# MICRO.net
KiCad netlist of a schematic drawn in Altium Designer
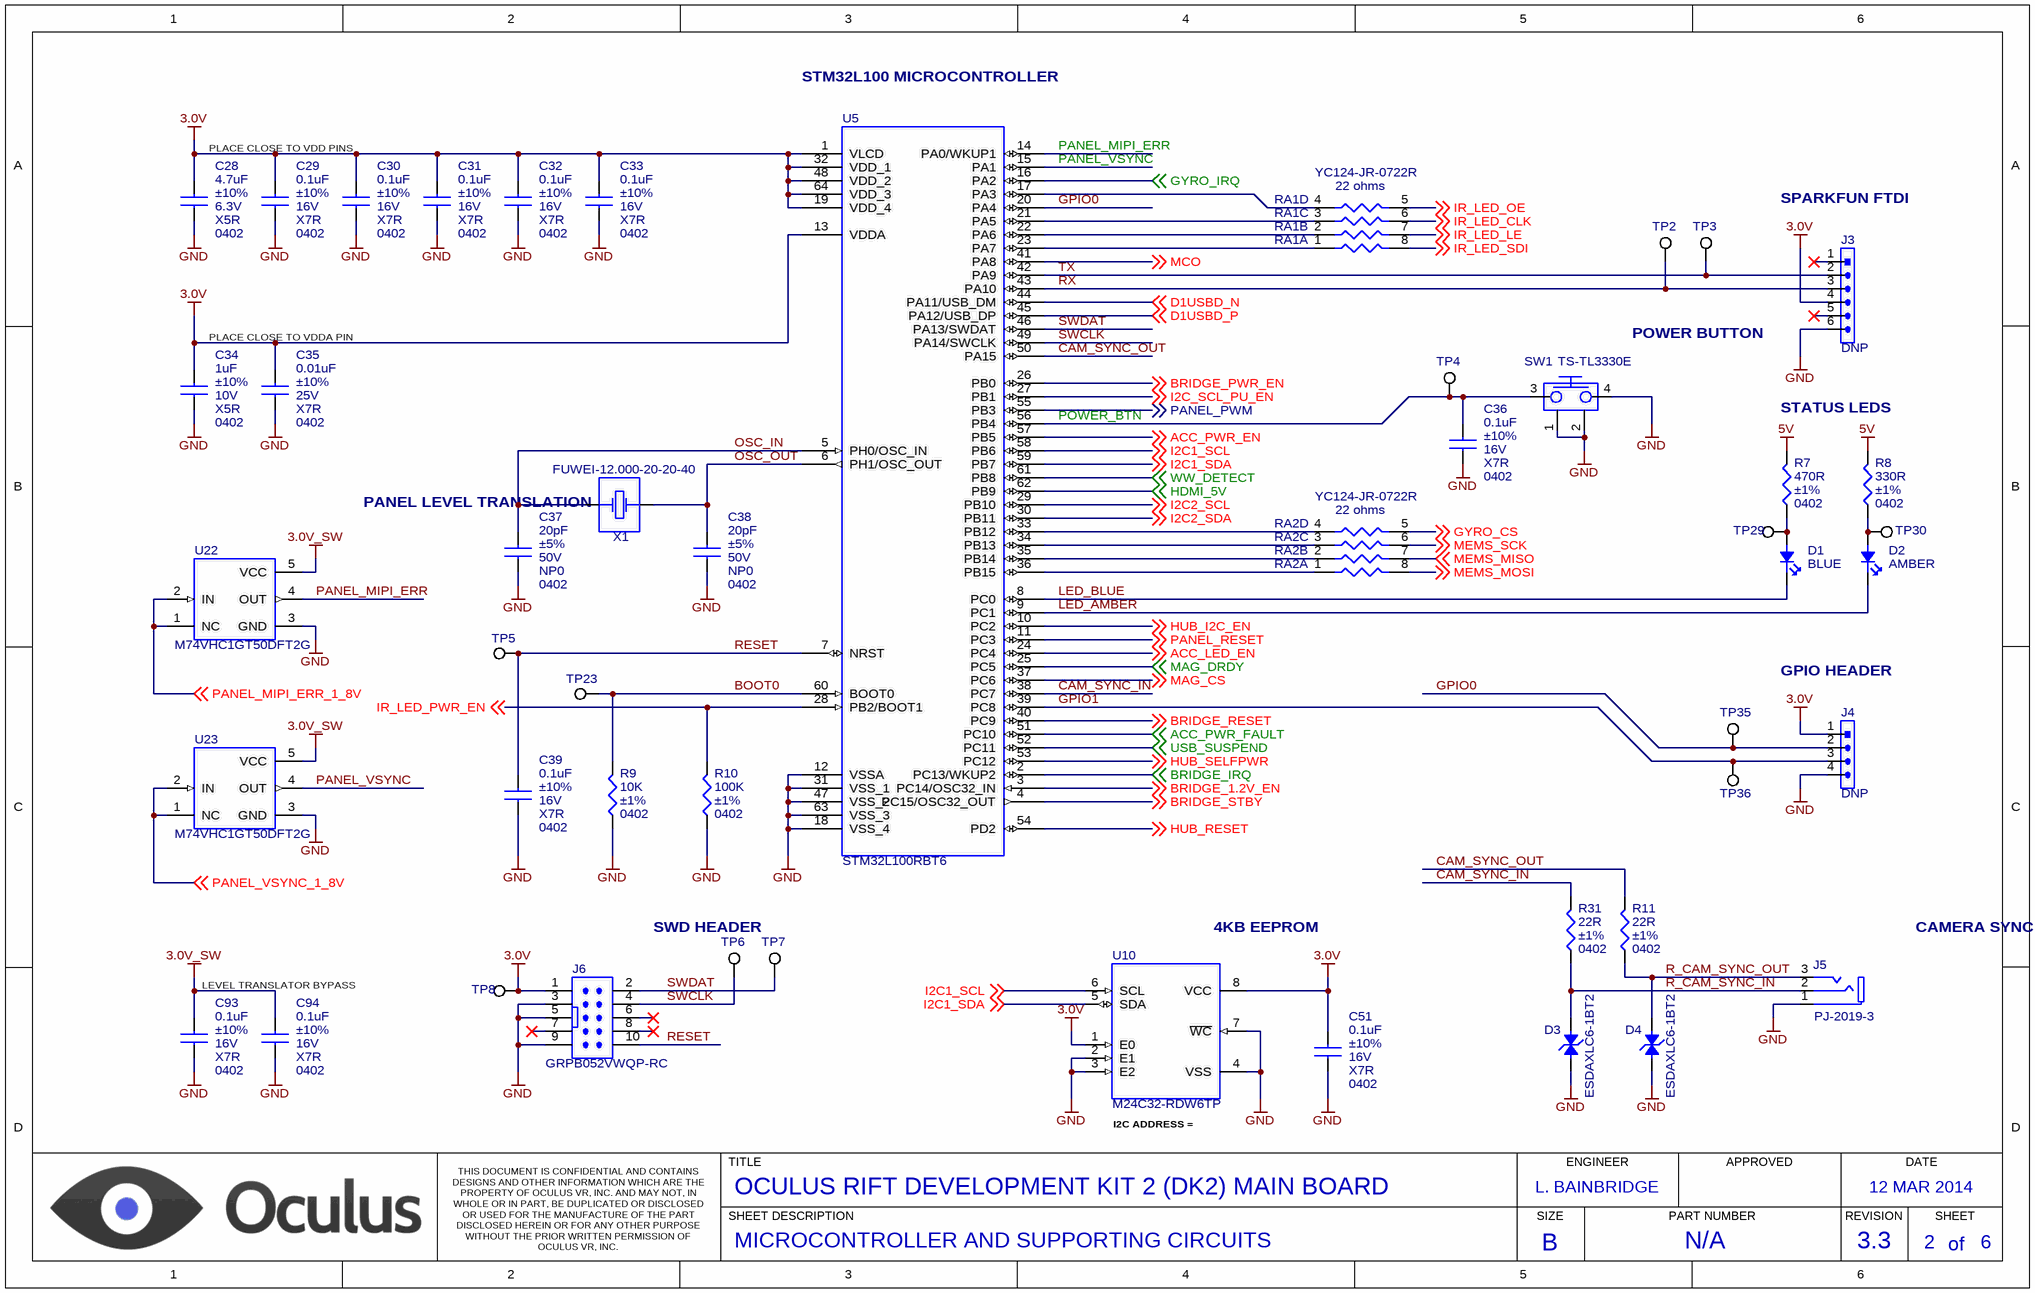
[diagram p0: MICRO.SchDoc]

(export (version "E")
  (design (tool "Eeschema 10.0.6"))
  (components
    (comp (ref "C28")
      (value "4.7uF")
      (footprint "CAP_CERAMIC_0402")
      (description "CAP, CERAMIC, 4.7uF, ±10%, 6.3V, X5R, 0402")
      (fields
        (field (name "MANUFACTURER") "TDK CORPORATION")
        (field (name "PART NUMBER") "C1005X5R0J475K")
        (field (name "TOLERANCE") "±10%")
        (field (name "VOLTAGE") "6.3V")
        (field (name "DIELECTRIC") "X5R")
        (field (name "PACKAGE") "0402")
      )
      (libsource (lib "DK2") (part "CAP, CERAMIC"))
    )
    (comp (ref "C29")
      (value "0.1uF")
      (footprint "CAP_CERAMIC_0402")
      (description "CAP, CERAMIC, 0.1uF, ±10%, 16V, X7R, 0402")
      (fields
        (field (name "MANUFACTURER") "MURATA ELECTRONICS")
        (field (name "PART NUMBER") "GRM155R71C104KA88D")
        (field (name "TOLERANCE") "±10%")
        (field (name "VOLTAGE") "16V")
        (field (name "DIELECTRIC") "X7R")
        (field (name "PACKAGE") "0402")
      )
      (libsource (lib "DK2") (part "CAP, CERAMIC"))
    )
    (comp (ref "C30")
      (value "0.1uF")
      (footprint "CAP_CERAMIC_0402")
      (description "CAP, CERAMIC, 0.1uF, ±10%, 16V, X7R, 0402")
      (fields
        (field (name "MANUFACTURER") "MURATA ELECTRONICS")
        (field (name "PART NUMBER") "GRM155R71C104KA88D")
        (field (name "TOLERANCE") "±10%")
        (field (name "VOLTAGE") "16V")
        (field (name "DIELECTRIC") "X7R")
        (field (name "PACKAGE") "0402")
      )
      (libsource (lib "DK2") (part "CAP, CERAMIC"))
    )
    (comp (ref "C31")
      (value "0.1uF")
      (footprint "CAP_CERAMIC_0402")
      (description "CAP, CERAMIC, 0.1uF, ±10%, 16V, X7R, 0402")
      (fields
        (field (name "MANUFACTURER") "MURATA ELECTRONICS")
        (field (name "PART NUMBER") "GRM155R71C104KA88D")
        (field (name "TOLERANCE") "±10%")
        (field (name "VOLTAGE") "16V")
        (field (name "DIELECTRIC") "X7R")
        (field (name "PACKAGE") "0402")
      )
      (libsource (lib "DK2") (part "CAP, CERAMIC"))
    )
    (comp (ref "C32")
      (value "0.1uF")
      (footprint "CAP_CERAMIC_0402")
      (description "CAP, CERAMIC, 0.1uF, ±10%, 16V, X7R, 0402")
      (fields
        (field (name "MANUFACTURER") "MURATA ELECTRONICS")
        (field (name "PART NUMBER") "GRM155R71C104KA88D")
        (field (name "TOLERANCE") "±10%")
        (field (name "VOLTAGE") "16V")
        (field (name "DIELECTRIC") "X7R")
        (field (name "PACKAGE") "0402")
      )
      (libsource (lib "DK2") (part "CAP, CERAMIC"))
    )
    (comp (ref "C33")
      (value "0.1uF")
      (footprint "CAP_CERAMIC_0402")
      (description "CAP, CERAMIC, 0.1uF, ±10%, 16V, X7R, 0402")
      (fields
        (field (name "MANUFACTURER") "MURATA ELECTRONICS")
        (field (name "PART NUMBER") "GRM155R71C104KA88D")
        (field (name "TOLERANCE") "±10%")
        (field (name "VOLTAGE") "16V")
        (field (name "DIELECTRIC") "X7R")
        (field (name "PACKAGE") "0402")
      )
      (libsource (lib "DK2") (part "CAP, CERAMIC"))
    )
    (comp (ref "C34")
      (value "1uF")
      (footprint "CAP_CERAMIC_0402")
      (description "CAP, CERAMIC, 1uF, ±10%, 10V, X5R, 0402")
      (fields
        (field (name "MANUFACTURER") "MURATA ELECTRONICS")
        (field (name "PART NUMBER") "GRM155R61A105KE15D")
        (field (name "TOLERANCE") "±10%")
        (field (name "VOLTAGE") "10V")
        (field (name "DIELECTRIC") "X5R")
        (field (name "PACKAGE") "0402")
      )
      (libsource (lib "DK2") (part "CAP, CERAMIC"))
    )
    (comp (ref "C35")
      (value "0.01uF")
      (footprint "CAP_CERAMIC_0402")
      (description "CAP, CERAMIC, 0.01uF, ±10%, 25V, X7R, 0402")
      (fields
        (field (name "MANUFACTURER") "MURATA ELECTRONICS")
        (field (name "PART NUMBER") "GRM155R71E103KA01D")
        (field (name "TOLERANCE") "±10%")
        (field (name "VOLTAGE") "25V")
        (field (name "DIELECTRIC") "X7R")
        (field (name "PACKAGE") "0402")
      )
      (libsource (lib "DK2") (part "CAP, CERAMIC"))
    )
    (comp (ref "C36")
      (value "0.1uF")
      (footprint "CAP_CERAMIC_0402")
      (description "CAP, CERAMIC, 0.1uF, ±10%, 16V, X7R, 0402")
      (fields
        (field (name "MANUFACTURER") "MURATA ELECTRONICS")
        (field (name "PART NUMBER") "GRM155R71C104KA88D")
        (field (name "TOLERANCE") "±10%")
        (field (name "VOLTAGE") "16V")
        (field (name "DIELECTRIC") "X7R")
        (field (name "PACKAGE") "0402")
      )
      (libsource (lib "DK2") (part "CAP, CERAMIC"))
    )
    (comp (ref "C37")
      (value "20pF")
      (footprint "CAP_CERAMIC_0402")
      (description "CAP, CERAMIC, 20pF, ±5%, 50V, NP0, 0402")
      (fields
        (field (name "MANUFACTURER") "MURATA ELECTRONICS")
        (field (name "PART NUMBER") "GRM1555C1H200JA01D")
        (field (name "TOLERANCE") "±5%")
        (field (name "VOLTAGE") "50V")
        (field (name "DIELECTRIC") "NP0")
        (field (name "PACKAGE") "0402")
      )
      (libsource (lib "DK2") (part "CAP, CERAMIC"))
    )
    (comp (ref "C38")
      (value "20pF")
      (footprint "CAP_CERAMIC_0402")
      (description "CAP, CERAMIC, 20pF, ±5%, 50V, NP0, 0402")
      (fields
        (field (name "MANUFACTURER") "MURATA ELECTRONICS")
        (field (name "PART NUMBER") "GRM1555C1H200JA01D")
        (field (name "TOLERANCE") "±5%")
        (field (name "VOLTAGE") "50V")
        (field (name "DIELECTRIC") "NP0")
        (field (name "PACKAGE") "0402")
      )
      (libsource (lib "DK2") (part "CAP, CERAMIC"))
    )
    (comp (ref "C39")
      (value "0.1uF")
      (footprint "CAP_CERAMIC_0402")
      (description "CAP, CERAMIC, 0.1uF, ±10%, 16V, X7R, 0402")
      (fields
        (field (name "MANUFACTURER") "MURATA ELECTRONICS")
        (field (name "PART NUMBER") "GRM155R71C104KA88D")
        (field (name "TOLERANCE") "±10%")
        (field (name "VOLTAGE") "16V")
        (field (name "DIELECTRIC") "X7R")
        (field (name "PACKAGE") "0402")
      )
      (libsource (lib "DK2") (part "CAP, CERAMIC"))
    )
    (comp (ref "C51")
      (value "0.1uF")
      (footprint "CAP_CERAMIC_0402")
      (description "CAP, CERAMIC, 0.1uF, ±10%, 16V, X7R, 0402")
      (fields
        (field (name "MANUFACTURER") "MURATA ELECTRONICS")
        (field (name "PART NUMBER") "GRM155R71C104KA88D")
        (field (name "TOLERANCE") "±10%")
        (field (name "VOLTAGE") "16V")
        (field (name "DIELECTRIC") "X7R")
        (field (name "PACKAGE") "0402")
      )
      (libsource (lib "DK2") (part "CAP, CERAMIC"))
    )
    (comp (ref "C93")
      (value "0.1uF")
      (footprint "CAP_CERAMIC_0402")
      (description "CAP, CERAMIC, 0.1uF, ±10%, 16V, X7R, 0402")
      (fields
        (field (name "MANUFACTURER") "MURATA ELECTRONICS")
        (field (name "PART NUMBER") "GRM155R71C104KA88D")
        (field (name "TOLERANCE") "±10%")
        (field (name "VOLTAGE") "16V")
        (field (name "DIELECTRIC") "X7R")
        (field (name "PACKAGE") "0402")
      )
      (libsource (lib "DK2") (part "CAP, CERAMIC"))
    )
    (comp (ref "C94")
      (value "0.1uF")
      (footprint "CAP_CERAMIC_0402")
      (description "CAP, CERAMIC, 0.1uF, ±10%, 16V, X7R, 0402")
      (fields
        (field (name "MANUFACTURER") "MURATA ELECTRONICS")
        (field (name "PART NUMBER") "GRM155R71C104KA88D")
        (field (name "TOLERANCE") "±10%")
        (field (name "VOLTAGE") "16V")
        (field (name "DIELECTRIC") "X7R")
        (field (name "PACKAGE") "0402")
      )
      (libsource (lib "DK2") (part "CAP, CERAMIC"))
    )
    (comp (ref "D1")
      (value "LED")
      (footprint "LED_BLUE_0603")
      (description "LED, BLUE, 0603")
      (fields
        (field (name "MANUFACTURER") "PANASONIC")
        (field (name "PART NUMBER") "LNJ926W8CRA")
        (field (name "COLOR") "BLUE")
      )
      (libsource (lib "DK2") (part "LED"))
    )
    (comp (ref "D2")
      (value "LED")
      (footprint "LED_AMBER_0603")
      (description "LED, AMBER, 0603")
      (fields
        (field (name "MANUFACTURER") "PANASONIC")
        (field (name "PART NUMBER") "LNJ437W84RA")
        (field (name "COLOR") "AMBER")
      )
      (libsource (lib "DK2") (part "LED"))
    )
    (comp (ref "D3")
      (value "ESDAXLC6-1BT2")
      (footprint "SOD-882T")
      (description "DIODE, ESD SUPPRESSOR, SINGLE LINE BI-DIRECTIONAL, LOW CAPACITANCE")
      (fields (field (name "MANUFACTURER") "ST MICROELECTRONICS"))
      (libsource (lib "DK2") (part "ESDAXLC6-1BT2"))
    )
    (comp (ref "D4")
      (value "ESDAXLC6-1BT2")
      (footprint "SOD-882T")
      (description "DIODE, ESD SUPPRESSOR, SINGLE LINE BI-DIRECTIONAL, LOW CAPACITANCE")
      (fields (field (name "MANUFACTURER") "ST MICROELECTRONICS"))
      (libsource (lib "DK2") (part "ESDAXLC6-1BT2"))
    )
    (comp (ref "J3")
      (value "DNP")
      (footprint "HEADER_1X6")
      (description "CONNECTOR, HEADER, 6 POS, 1X6, 0.1\" PITCH")
      (fields (field (name "MANUFACTURER") "TBD"))
      (libsource (lib "DK2") (part "HEADER 1X6"))
    )
    (comp (ref "J4")
      (value "DNP")
      (footprint "HEADER_1X4")
      (description "CONNECTOR, HEADER, 4 POS, 1X4, 0.1\" PITCH")
      (fields (field (name "MANUFACTURER") "TBD"))
      (libsource (lib "DK2") (part "HEADER 1X4"))
    )
    (comp (ref "J5")
      (value "PJ-2019-3")
      (footprint "PJ-2019-3")
      (description "CONNECTOR, 2.5MM STEREO AUDIO JACK")
      (fields (field (name "MANUFACTURER") "BERWAY TECHNOLOGY"))
      (libsource (lib "DK2") (part "PJ-2019-3"))
    )
    (comp (ref "J6")
      (value "GRPB052VWQP-RC")
      (footprint "GRPB052VWQP-RC")
      (description "CONNECTOR, 10 POS, ARM CORTEX SWD HEADER")
      (fields (field (name "MANUFACTURER") "SULLINS CONNECTOR"))
      (libsource (lib "DK2") (part "GRPB052VWQP-RC"))
    )
    (comp (ref "R7")
      (value "470R")
      (footprint "RESISTOR_0402")
      (description "RES, 470 OHM, 1/10W, ±1%, 0402")
      (fields
        (field (name "MANUFACTURER") "PANASONIC")
        (field (name "PART NUMBER") "ERJ-2RKF4700X")
        (field (name "PACKAGE") "0402")
        (field (name "TOLERANCE") "±1%")
      )
      (libsource (lib "DK2") (part "RESISTOR"))
    )
    (comp (ref "R8")
      (value "330R")
      (footprint "RESISTOR_0402")
      (description "RES, 330 OHM, 1/10W, ±1%, 0402")
      (fields
        (field (name "MANUFACTURER") "PANASONIC")
        (field (name "PART NUMBER") "ERJ-2RKF3300X")
        (field (name "PACKAGE") "0402")
        (field (name "TOLERANCE") "±1%")
      )
      (libsource (lib "DK2") (part "RESISTOR"))
    )
    (comp (ref "R9")
      (value "10K")
      (footprint "RESISTOR_0402")
      (description "RES, 10K OHM, 1/10W, ±1%, 0402")
      (fields
        (field (name "MANUFACTURER") "PANASONIC")
        (field (name "PART NUMBER") "ERJ-2RKF1002X")
        (field (name "PACKAGE") "0402")
        (field (name "TOLERANCE") "±1%")
      )
      (libsource (lib "DK2") (part "RESISTOR"))
    )
    (comp (ref "R10")
      (value "100K")
      (footprint "RESISTOR_0402")
      (description "RES, 100K OHM, 1/10W, ±1%, 0402")
      (fields
        (field (name "MANUFACTURER") "PANASONIC")
        (field (name "PART NUMBER") "ERJ-2RKF1003X")
        (field (name "PACKAGE") "0402")
        (field (name "TOLERANCE") "±1%")
      )
      (libsource (lib "DK2") (part "RESISTOR"))
    )
    (comp (ref "R11")
      (value "22R")
      (footprint "RESISTOR_0402")
      (description "RES, 22 OHM, 1/10W, ±1%, 0402")
      (fields
        (field (name "MANUFACTURER") "PANASONIC")
        (field (name "PART NUMBER") "ERJ-2RKF22R0X")
        (field (name "PACKAGE") "0402")
        (field (name "TOLERANCE") "±1%")
      )
      (libsource (lib "DK2") (part "RESISTOR"))
    )
    (comp (ref "R31")
      (value "22R")
      (footprint "RESISTOR_0402")
      (description "RES, 22 OHM, 1/10W, ±1%, 0402")
      (fields
        (field (name "MANUFACTURER") "PANASONIC")
        (field (name "PART NUMBER") "ERJ-2RKF22R0X")
        (field (name "PACKAGE") "0402")
        (field (name "TOLERANCE") "±1%")
      )
      (libsource (lib "DK2") (part "RESISTOR"))
    )
    (comp (ref "RA1")
      (value "YC124-JR-0722R")
      (footprint "YC124")
      (description "RESISTOR ARRAY, 4 RESISTORS, 22 OHM, 5%, 0.5MM PITCH")
      (fields (field (name "MANUFACTURER") "YAGEO") (field (name "ALTIUM_VALUE") "22 ohms"))
      (libsource (lib "DK2") (part "YC124-JR-0722R"))
    )
    (comp (ref "RA2")
      (value "YC124-JR-0722R")
      (footprint "YC124")
      (description "RESISTOR ARRAY, 4 RESISTORS, 22 OHM, 5%, 0.5MM PITCH")
      (fields (field (name "MANUFACTURER") "YAGEO") (field (name "ALTIUM_VALUE") "22 ohms"))
      (libsource (lib "DK2") (part "YC124-JR-0722R"))
    )
    (comp (ref "SW1")
      (value "TS-TL3330E")
      (footprint "TS-TL3330E")
      (description "SWITCH, TACTILE, SPST-NO, 250gf")
      (fields (field (name "MANUFACTURER") "BERWAY TECHNOLOGY"))
      (libsource (lib "DK2") (part "TS-TL3330E"))
    )
    (comp (ref "TP2")
      (value "TEST POINT")
      (footprint "TEST_POINT_PAD_1.2X3MM")
      (libsource (lib "DK2") (part "TEST_POINT_GENERIC"))
    )
    (comp (ref "TP3")
      (value "TEST POINT")
      (footprint "TEST_POINT_PAD_1.2X3MM")
      (libsource (lib "DK2") (part "TEST_POINT_GENERIC"))
    )
    (comp (ref "TP4")
      (value "TEST POINT")
      (footprint "TEST_POINT_PAD_1MM")
      (libsource (lib "DK2") (part "TEST_POINT_GENERIC"))
    )
    (comp (ref "TP5")
      (value "TEST POINT")
      (footprint "TEST_POINT_PAD_1MM")
      (libsource (lib "DK2") (part "TEST_POINT_GENERIC"))
    )
    (comp (ref "TP6")
      (value "TEST POINT")
      (footprint "TEST_POINT_PAD_1MM")
      (libsource (lib "DK2") (part "TEST_POINT_GENERIC"))
    )
    (comp (ref "TP7")
      (value "TEST POINT")
      (footprint "TEST_POINT_PAD_1MM")
      (libsource (lib "DK2") (part "TEST_POINT_GENERIC"))
    )
    (comp (ref "TP8")
      (value "TEST POINT")
      (footprint "TEST_POINT_PAD_1MM")
      (libsource (lib "DK2") (part "TEST_POINT_GENERIC"))
    )
    (comp (ref "TP23")
      (value "TEST POINT")
      (footprint "TEST_POINT_PAD_1MM")
      (libsource (lib "DK2") (part "TEST_POINT_GENERIC"))
    )
    (comp (ref "TP29")
      (value "TEST POINT")
      (footprint "TEST_POINT_PAD_1MM")
      (libsource (lib "DK2") (part "TEST_POINT_GENERIC"))
    )
    (comp (ref "TP30")
      (value "TEST POINT")
      (footprint "TEST_POINT_PAD_1MM")
      (libsource (lib "DK2") (part "TEST_POINT_GENERIC"))
    )
    (comp (ref "TP35")
      (value "TEST POINT")
      (footprint "TEST_POINT_PAD_1.2X3MM")
      (libsource (lib "DK2") (part "TEST_POINT_GENERIC"))
    )
    (comp (ref "TP36")
      (value "TEST POINT")
      (footprint "TEST_POINT_PAD_1MM")
      (libsource (lib "DK2") (part "TEST_POINT_GENERIC"))
    )
    (comp (ref "U5")
      (value "STM32L100RBT6")
      (footprint "LQFP64")
      (description "IC, STM32L MICROCONTROLLER, ARM CORTEX M3")
      (fields (field (name "MANUFACTURER") "ST MICROELECTRONICS"))
      (libsource (lib "DK2") (part "STM32L100RBT6"))
    )
    (comp (ref "U10")
      (value "M24C32-RDW6TP")
      (footprint "TSSOP8")
      (description "IC, EEPROM, I2C, 32 Kbits")
      (fields (field (name "MANUFACTURER") "STMICROELECTRONICS"))
      (libsource (lib "DK2") (part "M24C32-RDW6TP"))
    )
    (comp (ref "U22")
      (value "M74VHC1GT50DFT2G")
      (footprint "SC70-5")
      (description "IC, NON-INVERTING BUFFER, CMOS LOGIC LEVEL SHIFTER")
      (fields (field (name "MANUFACTURER") "ON SEMICONDUCTOR"))
      (libsource (lib "DK2") (part "M74VHC1GT50DFT2G"))
    )
    (comp (ref "U23")
      (value "M74VHC1GT50DFT2G")
      (footprint "SC70-5")
      (description "IC, NON-INVERTING BUFFER, CMOS LOGIC LEVEL SHIFTER")
      (fields (field (name "MANUFACTURER") "ON SEMICONDUCTOR"))
      (libsource (lib "DK2") (part "M74VHC1GT50DFT2G"))
    )
    (comp (ref "X1")
      (value "FUWEI-12.000-20-20-40")
      (footprint "HC-49USX")
      (description "CRYSTAL, 12MHZ, +/-30PPM, 20pF, HC-49USX")
      (fields (field (name "MANUFACTURER") "BERWAY TECHNOLOGY"))
      (libsource (lib "DK2") (part "FUWEI-12.000-20-20-40"))
    )
  )
  (nets
    (net (code "1") (name "/BOOT0") (class "Default")
      (node (ref "R9") (pin "2") (pinfunction "2_2") (pintype "passive"))
      (node (ref "TP23") (pin "1") (pinfunction "1_1") (pintype "passive"))
      (node (ref "U5") (pin "60") (pinfunction "BOOT0_60") (pintype "input"))
    )
    (net (code "2") (name "/CAM_SYNC_IN") (class "Default")
      (node (ref "R31") (pin "1") (pinfunction "1_1") (pintype "passive"))
      (node (ref "U5") (pin "38") (pinfunction "PC7_38") (pintype "bidirectional"))
    )
    (net (code "3") (name "/CAM_SYNC_OUT") (class "Default")
      (node (ref "R11") (pin "1") (pinfunction "1_1") (pintype "passive"))
      (node (ref "U5") (pin "50") (pinfunction "PA15_50") (pintype "bidirectional"))
    )
    (net (code "4") (name "/GPIO0") (class "Default")
      (node (ref "J4") (pin "2") (pintype "passive"))
      (node (ref "TP35") (pin "1") (pinfunction "1_1") (pintype "passive"))
      (node (ref "U5") (pin "20") (pinfunction "PA4_20") (pintype "bidirectional"))
    )
    (net (code "5") (name "/GPIO1") (class "Default")
      (node (ref "J4") (pin "3") (pintype "passive"))
      (node (ref "TP36") (pin "1") (pinfunction "1_1") (pintype "passive"))
      (node (ref "U5") (pin "39") (pinfunction "PC8_39") (pintype "bidirectional"))
    )
    (net (code "6") (name "/LED_AMBER") (class "Default")
      (node (ref "D2") (pin "2") (pinfunction "K_2") (pintype "passive"))
      (node (ref "U5") (pin "9") (pinfunction "PC1_9") (pintype "bidirectional"))
    )
    (net (code "7") (name "/LED_BLUE") (class "Default")
      (node (ref "D1") (pin "2") (pinfunction "K_2") (pintype "passive"))
      (node (ref "U5") (pin "8") (pinfunction "PC0_8") (pintype "bidirectional"))
    )
    (net (code "8") (name "/OSC_IN") (class "Default")
      (node (ref "C37") (pin "1") (pinfunction "1_1") (pintype "passive"))
      (node (ref "U5") (pin "5") (pinfunction "PH0/OSC_IN_5") (pintype "input"))
      (node (ref "X1") (pin "1") (pinfunction "1_1") (pintype "passive"))
    )
    (net (code "9") (name "/OSC_OUT") (class "Default")
      (node (ref "C38") (pin "1") (pinfunction "1_1") (pintype "passive"))
      (node (ref "U5") (pin "6") (pinfunction "PH1/OSC_OUT_6") (pintype "output"))
      (node (ref "X1") (pin "2") (pinfunction "3_2") (pintype "passive"))
    )
    (net (code "10") (name "/PANEL_MIPI_ERR") (class "Default")
      (node (ref "U22") (pin "4") (pinfunction "OUT_4") (pintype "output"))
      (node (ref "U5") (pin "14") (pinfunction "PA0/WKUP1_14") (pintype "bidirectional"))
    )
    (net (code "11") (name "/PANEL_VSYNC") (class "Default")
      (node (ref "U23") (pin "4") (pinfunction "OUT_4") (pintype "output"))
      (node (ref "U5") (pin "15") (pinfunction "PA1_15") (pintype "bidirectional"))
    )
    (net (code "12") (name "/POWER_BTN") (class "Default")
      (node (ref "C36") (pin "1") (pinfunction "1_1") (pintype "passive"))
      (node (ref "SW1") (pin "3") (pintype "passive"))
      (node (ref "TP4") (pin "1") (pinfunction "1_1") (pintype "passive"))
      (node (ref "U5") (pin "56") (pinfunction "PB4_56") (pintype "bidirectional"))
    )
    (net (code "13") (name "/RESET") (class "Default")
      (node (ref "C39") (pin "1") (pinfunction "1_1") (pintype "passive"))
      (node (ref "J6") (pin "10") (pintype "passive"))
      (node (ref "TP5") (pin "1") (pinfunction "1_1") (pintype "passive"))
      (node (ref "U5") (pin "7") (pinfunction "NRST_7") (pintype "bidirectional"))
    )
    (net (code "14") (name "/RX") (class "Default")
      (node (ref "J3") (pin "3") (pintype "passive"))
      (node (ref "TP2") (pin "1") (pinfunction "1_1") (pintype "passive"))
      (node (ref "U5") (pin "43") (pinfunction "PA10_43") (pintype "bidirectional"))
    )
    (net (code "15") (name "/R_CAM_SYNC_IN") (class "Default")
      (node (ref "D3") (pin "1") (pintype "passive"))
      (node (ref "J5") (pin "2") (pinfunction "2_2") (pintype "passive"))
      (node (ref "R31") (pin "2") (pinfunction "2_2") (pintype "passive"))
    )
    (net (code "16") (name "/R_CAM_SYNC_OUT") (class "Default")
      (node (ref "D4") (pin "1") (pintype "passive"))
      (node (ref "J5") (pin "3") (pinfunction "3_3") (pintype "passive"))
      (node (ref "R11") (pin "2") (pinfunction "2_2") (pintype "passive"))
    )
    (net (code "17") (name "/SWCLK") (class "Default")
      (node (ref "J6") (pin "4") (pintype "passive"))
      (node (ref "TP6") (pin "1") (pinfunction "1_1") (pintype "passive"))
      (node (ref "U5") (pin "49") (pinfunction "PA14/SWCLK_49") (pintype "bidirectional"))
    )
    (net (code "18") (name "/SWDAT") (class "Default")
      (node (ref "J6") (pin "2") (pintype "passive"))
      (node (ref "TP7") (pin "1") (pinfunction "1_1") (pintype "passive"))
      (node (ref "U5") (pin "46") (pinfunction "PA13/SWDAT_46") (pintype "bidirectional"))
    )
    (net (code "19") (name "/TX") (class "Default")
      (node (ref "J3") (pin "2") (pintype "passive"))
      (node (ref "TP3") (pin "1") (pinfunction "1_1") (pintype "passive"))
      (node (ref "U5") (pin "42") (pinfunction "PA9_42") (pintype "bidirectional"))
    )
    (net (code "20") (name "3.0V") (class "Default")
      (node (ref "C28") (pin "1") (pinfunction "1_1") (pintype "passive"))
      (node (ref "C29") (pin "1") (pinfunction "1_1") (pintype "passive"))
      (node (ref "C30") (pin "1") (pinfunction "1_1") (pintype "passive"))
      (node (ref "C31") (pin "1") (pinfunction "1_1") (pintype "passive"))
      (node (ref "C32") (pin "1") (pinfunction "1_1") (pintype "passive"))
      (node (ref "C33") (pin "1") (pinfunction "1_1") (pintype "passive"))
      (node (ref "C34") (pin "1") (pinfunction "1_1") (pintype "passive"))
      (node (ref "C35") (pin "1") (pinfunction "1_1") (pintype "passive"))
      (node (ref "C51") (pin "1") (pinfunction "1_1") (pintype "passive"))
      (node (ref "J3") (pin "4") (pintype "passive"))
      (node (ref "J4") (pin "1") (pintype "passive"))
      (node (ref "J6") (pin "1") (pintype "passive"))
      (node (ref "TP8") (pin "1") (pinfunction "1_1") (pintype "passive"))
      (node (ref "U10") (pin "1") (pinfunction "E0_1") (pintype "input"))
      (node (ref "U10") (pin "8") (pinfunction "VCC_8") (pintype "power_in"))
      (node (ref "U5") (pin "1") (pinfunction "VLCD_1") (pintype "power_in"))
      (node (ref "U5") (pin "13") (pinfunction "VDDA_13") (pintype "power_in"))
      (node (ref "U5") (pin "19") (pinfunction "VDD_4_19") (pintype "power_in"))
      (node (ref "U5") (pin "32") (pinfunction "VDD_1_32") (pintype "power_in"))
      (node (ref "U5") (pin "48") (pinfunction "VDD_2_48") (pintype "power_in"))
      (node (ref "U5") (pin "64") (pinfunction "VDD_3_64") (pintype "power_in"))
    )
    (net (code "21") (name "3.0V_SW") (class "Default")
      (node (ref "C93") (pin "1") (pinfunction "1_1") (pintype "passive"))
      (node (ref "C94") (pin "1") (pinfunction "1_1") (pintype "passive"))
      (node (ref "U22") (pin "5") (pinfunction "VCC_5") (pintype "power_in"))
      (node (ref "U23") (pin "5") (pinfunction "VCC_5") (pintype "power_in"))
    )
    (net (code "22") (name "5V") (class "Default")
      (node (ref "R7") (pin "2") (pinfunction "2_2") (pintype "passive"))
      (node (ref "R8") (pin "2") (pinfunction "2_2") (pintype "passive"))
    )
    (net (code "23") (name "ACC_LED_EN") (class "Default")
      (node (ref "U5") (pin "24") (pinfunction "PC4_24") (pintype "bidirectional"))
    )
    (net (code "24") (name "ACC_PWR_EN") (class "Default")
      (node (ref "U5") (pin "57") (pinfunction "PB5_57") (pintype "bidirectional"))
    )
    (net (code "25") (name "ACC_PWR_FAULT") (class "Default")
      (node (ref "U5") (pin "51") (pinfunction "PC10_51") (pintype "bidirectional"))
    )
    (net (code "26") (name "BRIDGE_1.2V_EN") (class "Default")
      (node (ref "U5") (pin "3") (pinfunction "PC14/OSC32_IN_3") (pintype "input"))
    )
    (net (code "27") (name "BRIDGE_IRQ") (class "Default")
      (node (ref "U5") (pin "2") (pinfunction "PC13/WKUP2_2") (pintype "bidirectional"))
    )
    (net (code "28") (name "BRIDGE_PWR_EN") (class "Default")
      (node (ref "U5") (pin "26") (pinfunction "PB0_26") (pintype "bidirectional"))
    )
    (net (code "29") (name "BRIDGE_RESET") (class "Default")
      (node (ref "U5") (pin "40") (pinfunction "PC9_40") (pintype "bidirectional"))
    )
    (net (code "30") (name "BRIDGE_STBY") (class "Default")
      (node (ref "U5") (pin "4") (pinfunction "PC15/OSC32_OUT_4") (pintype "output"))
    )
    (net (code "31") (name "D1USBD_N") (class "Default")
      (node (ref "U5") (pin "44") (pinfunction "PA11/USB_DM_44") (pintype "bidirectional"))
    )
    (net (code "32") (name "D1USBD_P") (class "Default")
      (node (ref "U5") (pin "45") (pinfunction "PA12/USB_DP_45") (pintype "bidirectional"))
    )
    (net (code "33") (name "GND") (class "Default")
      (node (ref "C28") (pin "2") (pinfunction "2_2") (pintype "passive"))
      (node (ref "C29") (pin "2") (pinfunction "2_2") (pintype "passive"))
      (node (ref "C30") (pin "2") (pinfunction "2_2") (pintype "passive"))
      (node (ref "C31") (pin "2") (pinfunction "2_2") (pintype "passive"))
      (node (ref "C32") (pin "2") (pinfunction "2_2") (pintype "passive"))
      (node (ref "C33") (pin "2") (pinfunction "2_2") (pintype "passive"))
      (node (ref "C34") (pin "2") (pinfunction "2_2") (pintype "passive"))
      (node (ref "C35") (pin "2") (pinfunction "2_2") (pintype "passive"))
      (node (ref "C36") (pin "2") (pinfunction "2_2") (pintype "passive"))
      (node (ref "C37") (pin "2") (pinfunction "2_2") (pintype "passive"))
      (node (ref "C38") (pin "2") (pinfunction "2_2") (pintype "passive"))
      (node (ref "C39") (pin "2") (pinfunction "2_2") (pintype "passive"))
      (node (ref "C51") (pin "2") (pinfunction "2_2") (pintype "passive"))
      (node (ref "C93") (pin "2") (pinfunction "2_2") (pintype "passive"))
      (node (ref "C94") (pin "2") (pinfunction "2_2") (pintype "passive"))
      (node (ref "D3") (pin "2") (pintype "passive"))
      (node (ref "D4") (pin "2") (pintype "passive"))
      (node (ref "J3") (pin "6") (pintype "passive"))
      (node (ref "J4") (pin "4") (pintype "passive"))
      (node (ref "J5") (pin "1") (pinfunction "1_1") (pintype "passive"))
      (node (ref "J6") (pin "3") (pintype "passive"))
      (node (ref "J6") (pin "5") (pintype "passive"))
      (node (ref "J6") (pin "9") (pintype "passive"))
      (node (ref "R10") (pin "1") (pinfunction "1_1") (pintype "passive"))
      (node (ref "R9") (pin "1") (pinfunction "1_1") (pintype "passive"))
      (node (ref "SW1") (pin "1") (pintype "passive"))
      (node (ref "SW1") (pin "2") (pintype "passive"))
      (node (ref "SW1") (pin "4") (pintype "passive"))
      (node (ref "U10") (pin "2") (pinfunction "E1_2") (pintype "input"))
      (node (ref "U10") (pin "3") (pinfunction "E2_3") (pintype "input"))
      (node (ref "U10") (pin "4") (pinfunction "VSS_4") (pintype "power_in"))
      (node (ref "U10") (pin "7") (pinfunction "~{WC}_7") (pintype "input"))
      (node (ref "U22") (pin "3") (pinfunction "GND_3") (pintype "power_in"))
      (node (ref "U23") (pin "3") (pinfunction "GND_3") (pintype "power_in"))
      (node (ref "U5") (pin "12") (pinfunction "VSSA_12") (pintype "power_in"))
      (node (ref "U5") (pin "18") (pinfunction "VSS_4_18") (pintype "power_in"))
      (node (ref "U5") (pin "31") (pinfunction "VSS_1_31") (pintype "power_in"))
      (node (ref "U5") (pin "47") (pinfunction "VSS_2_47") (pintype "power_in"))
      (node (ref "U5") (pin "63") (pinfunction "VSS_3_63") (pintype "power_in"))
    )
    (net (code "34") (name "GYRO_CS") (class "Default") (node (ref "RA2") (pin "5") (pintype "passive")))
    (net (code "35") (name "GYRO_IRQ") (class "Default")
      (node (ref "U5") (pin "16") (pinfunction "PA2_16") (pintype "bidirectional"))
    )
    (net (code "36") (name "HDMI_5V") (class "Default")
      (node (ref "U5") (pin "62") (pinfunction "PB9_62") (pintype "bidirectional"))
    )
    (net (code "37") (name "HUB_I2C_EN") (class "Default")
      (node (ref "U5") (pin "10") (pinfunction "PC2_10") (pintype "bidirectional"))
    )
    (net (code "38") (name "HUB_RESET") (class "Default")
      (node (ref "U5") (pin "54") (pinfunction "PD2_54") (pintype "bidirectional"))
    )
    (net (code "39") (name "HUB_SELFPWR") (class "Default")
      (node (ref "U5") (pin "53") (pinfunction "PC12_53") (pintype "bidirectional"))
    )
    (net (code "40") (name "I2C1_SCL") (class "Default")
      (node (ref "U10") (pin "6") (pinfunction "SCL_6") (pintype "input"))
      (node (ref "U5") (pin "58") (pinfunction "PB6_58") (pintype "bidirectional"))
    )
    (net (code "41") (name "I2C1_SDA") (class "Default")
      (node (ref "U10") (pin "5") (pinfunction "SDA_5") (pintype "bidirectional"))
      (node (ref "U5") (pin "59") (pinfunction "PB7_59") (pintype "bidirectional"))
    )
    (net (code "42") (name "I2C2_SCL") (class "Default")
      (node (ref "U5") (pin "29") (pinfunction "PB10_29") (pintype "bidirectional"))
    )
    (net (code "43") (name "I2C2_SDA") (class "Default")
      (node (ref "U5") (pin "30") (pinfunction "PB11_30") (pintype "bidirectional"))
    )
    (net (code "44") (name "I2C_SCL_PU_EN") (class "Default")
      (node (ref "U5") (pin "27") (pinfunction "PB1_27") (pintype "bidirectional"))
    )
    (net (code "45") (name "IR_LED_CLK") (class "Default") (node (ref "RA1") (pin "6") (pintype "passive")))
    (net (code "46") (name "IR_LED_LE") (class "Default") (node (ref "RA1") (pin "7") (pintype "passive")))
    (net (code "47") (name "IR_LED_OE") (class "Default") (node (ref "RA1") (pin "5") (pintype "passive")))
    (net (code "48") (name "IR_LED_PWR_EN") (class "Default")
      (node (ref "R10") (pin "2") (pinfunction "2_2") (pintype "passive"))
      (node (ref "U5") (pin "28") (pinfunction "PB2/BOOT1_28") (pintype "input"))
    )
    (net (code "49") (name "IR_LED_SDI") (class "Default") (node (ref "RA1") (pin "8") (pintype "passive")))
    (net (code "50") (name "MAG_CS") (class "Default")
      (node (ref "U5") (pin "37") (pinfunction "PC6_37") (pintype "bidirectional"))
    )
    (net (code "51") (name "MAG_DRDY") (class "Default")
      (node (ref "U5") (pin "25") (pinfunction "PC5_25") (pintype "bidirectional"))
    )
    (net (code "52") (name "MCO") (class "Default")
      (node (ref "U5") (pin "41") (pinfunction "PA8_41") (pintype "bidirectional"))
    )
    (net (code "53") (name "MEMS_MISO") (class "Default") (node (ref "RA2") (pin "7") (pintype "passive")))
    (net (code "54") (name "MEMS_MOSI") (class "Default") (node (ref "RA2") (pin "8") (pintype "passive")))
    (net (code "55") (name "MEMS_SCK") (class "Default") (node (ref "RA2") (pin "6") (pintype "passive")))
    (net (code "56") (name "Net-(D1-A)") (class "Default")
      (node (ref "D1") (pin "1") (pinfunction "A_1") (pintype "passive"))
      (node (ref "R7") (pin "1") (pinfunction "1_1") (pintype "passive"))
      (node (ref "TP29") (pin "1") (pinfunction "1_1") (pintype "passive"))
    )
    (net (code "57") (name "Net-(D2-A)") (class "Default")
      (node (ref "D2") (pin "1") (pinfunction "A_1") (pintype "passive"))
      (node (ref "R8") (pin "1") (pinfunction "1_1") (pintype "passive"))
      (node (ref "TP30") (pin "1") (pinfunction "1_1") (pintype "passive"))
    )
    (net (code "58") (name "Net-(U5-PA3)") (class "Default")
      (node (ref "RA1") (pin "4") (pintype "passive"))
      (node (ref "U5") (pin "17") (pinfunction "PA3_17") (pintype "bidirectional"))
    )
    (net (code "59") (name "Net-(U5-PA5)") (class "Default")
      (node (ref "RA1") (pin "3") (pintype "passive"))
      (node (ref "U5") (pin "21") (pinfunction "PA5_21") (pintype "bidirectional"))
    )
    (net (code "60") (name "Net-(U5-PA6)") (class "Default")
      (node (ref "RA1") (pin "2") (pintype "passive"))
      (node (ref "U5") (pin "22") (pinfunction "PA6_22") (pintype "bidirectional"))
    )
    (net (code "61") (name "Net-(U5-PA7)") (class "Default")
      (node (ref "RA1") (pin "1") (pintype "passive"))
      (node (ref "U5") (pin "23") (pinfunction "PA7_23") (pintype "bidirectional"))
    )
    (net (code "62") (name "Net-(U5-PB12)") (class "Default")
      (node (ref "RA2") (pin "4") (pintype "passive"))
      (node (ref "U5") (pin "33") (pinfunction "PB12_33") (pintype "bidirectional"))
    )
    (net (code "63") (name "Net-(U5-PB13)") (class "Default")
      (node (ref "RA2") (pin "3") (pintype "passive"))
      (node (ref "U5") (pin "34") (pinfunction "PB13_34") (pintype "bidirectional"))
    )
    (net (code "64") (name "Net-(U5-PB14)") (class "Default")
      (node (ref "RA2") (pin "2") (pintype "passive"))
      (node (ref "U5") (pin "35") (pinfunction "PB14_35") (pintype "bidirectional"))
    )
    (net (code "65") (name "Net-(U5-PB15)") (class "Default")
      (node (ref "RA2") (pin "1") (pintype "passive"))
      (node (ref "U5") (pin "36") (pinfunction "PB15_36") (pintype "bidirectional"))
    )
    (net (code "66") (name "PANEL_MIPI_ERR_1_8V") (class "Default")
      (node (ref "U22") (pin "1") (pinfunction "NC_1") (pintype "power_in"))
      (node (ref "U22") (pin "2") (pinfunction "IN_2") (pintype "input"))
    )
    (net (code "67") (name "PANEL_PWM") (class "Default")
      (node (ref "U5") (pin "55") (pinfunction "PB3_55") (pintype "bidirectional"))
    )
    (net (code "68") (name "PANEL_RESET") (class "Default")
      (node (ref "U5") (pin "11") (pinfunction "PC3_11") (pintype "bidirectional"))
    )
    (net (code "69") (name "PANEL_VSYNC_1_8V") (class "Default")
      (node (ref "U23") (pin "1") (pinfunction "NC_1") (pintype "power_in"))
      (node (ref "U23") (pin "2") (pinfunction "IN_2") (pintype "input"))
    )
    (net (code "70") (name "USB_SUSPEND") (class "Default")
      (node (ref "U5") (pin "52") (pinfunction "PC11_52") (pintype "bidirectional"))
    )
    (net (code "71") (name "WW_DETECT") (class "Default")
      (node (ref "U5") (pin "61") (pinfunction "PB8_61") (pintype "bidirectional"))
    )
    (net (code "72") (name "unconnected-(J3-Pad1)") (class "Default")
      (node (ref "J3") (pin "1") (pintype "passive+no_connect"))
    )
    (net (code "73") (name "unconnected-(J3-Pad5)") (class "Default")
      (node (ref "J3") (pin "5") (pintype "passive+no_connect"))
    )
    (net (code "74") (name "unconnected-(J6-Pad6)") (class "Default")
      (node (ref "J6") (pin "6") (pintype "passive+no_connect"))
    )
    (net (code "75") (name "unconnected-(J6-Pad7)") (class "Default")
      (node (ref "J6") (pin "7") (pintype "passive+no_connect"))
    )
    (net (code "76") (name "unconnected-(J6-Pad8)") (class "Default")
      (node (ref "J6") (pin "8") (pintype "passive+no_connect"))
    )
  )
)
